# board.net
KiCad netlist of a schematic drawn in EAGLE
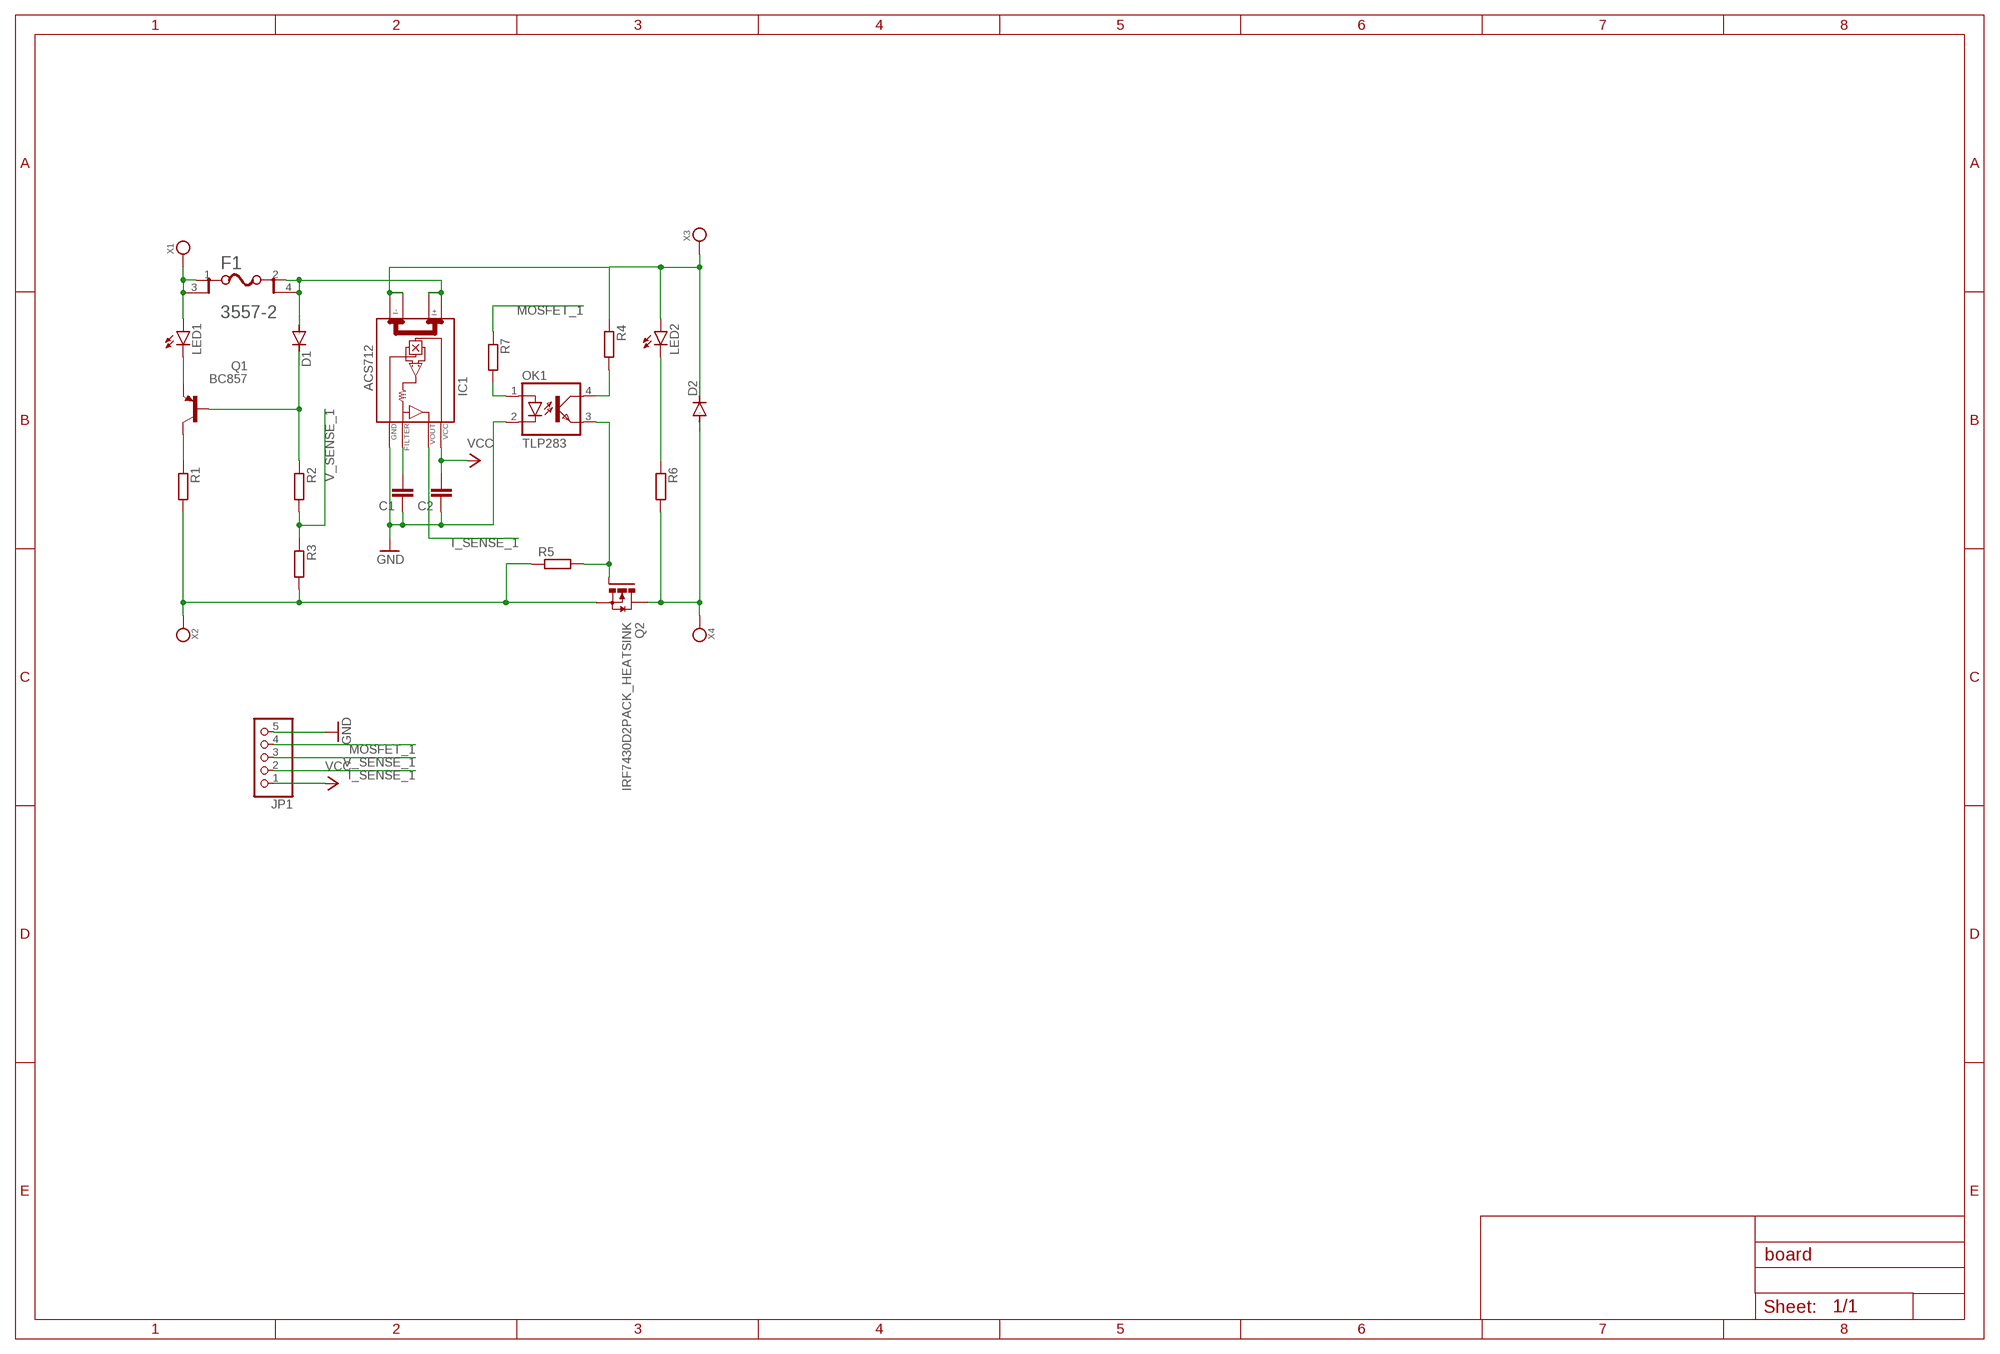
[diagram p0: schematic, sheet 1]

(export (version "E")
  (design (tool "Eeschema 10.0.6"))
  (components
    (comp (ref "C1")
      (value "C-EUC0805")
      (footprint "eagle-import:C0805")
      (libsource (lib "eagle-import") (part "C-EUC0805"))
    )
    (comp (ref "C2")
      (value "C-EUC0805")
      (footprint "eagle-import:C0805")
      (libsource (lib "eagle-import") (part "C-EUC0805"))
    )
    (comp (ref "D1")
      (value "DIODE-SOD123")
      (footprint "eagle-import:DIODE_SOD123")
      (libsource (lib "eagle-import") (part "DIODE-SOD123"))
    )
    (comp (ref "D2")
      (value "DIODE-DO214AC")
      (footprint "eagle-import:DO214AC")
      (libsource (lib "eagle-import") (part "diode_210_DIODE-DO214AC"))
    )
    (comp (ref "F1")
      (value "KEYSTONE_3557-2KEYSTONE_3557-2_0_0")
      (footprint "eagle-import:KEYSTONE_3557-2_0")
      (fields
        (field (name "DIGIKEY_PART_NUMBER") "36-3557-2-ND")
        (field (name "MF") "Keystone")
        (field (name "MOUSER_PART_NUMBER") "534-3557-2")
      )
      (libsource (lib "eagle-import") (part "KEYSTONE_3557-2KEYSTONE_3557-2_0_0"))
    )
    (comp (ref "IC1")
      (value "ACS712")
      (footprint "eagle-import:SO08")
      (libsource (lib "eagle-import") (part "ACS712"))
    )
    (comp (ref "JP1")
      (value "PINHD-1X5")
      (footprint "eagle-import:1X05")
      (libsource (lib "eagle-import") (part "PINHD-1X5"))
    )
    (comp (ref "LED1")
      (value "LEDSMT1206")
      (footprint "eagle-import:1206")
      (libsource (lib "eagle-import") (part "LEDSMT1206"))
    )
    (comp (ref "LED2")
      (value "LEDSMT1206")
      (footprint "eagle-import:1206")
      (libsource (lib "eagle-import") (part "LEDSMT1206"))
    )
    (comp (ref "OK1")
      (value "TLP283")
      (footprint "eagle-import:MINI-FLAT-4")
      (libsource (lib "eagle-import") (part "TLP283"))
    )
    (comp (ref "Q1")
      (value "BC857")
      (footprint "eagle-import:SOT23-BEC")
      (libsource (lib "eagle-import") (part "BC857SMDA"))
    )
    (comp (ref "Q2")
      (value "IRF7430D2PACK_HEATSINK")
      (footprint "eagle-import:D2PACK_HEATSINK")
      (libsource (lib "eagle-import") (part "IRF7430D2PACK_HEATSINK"))
    )
    (comp (ref "R1")
      (value "R-EU_R0805")
      (footprint "eagle-import:R0805")
      (libsource (lib "eagle-import") (part "R-EU_R0805"))
    )
    (comp (ref "R2")
      (value "R-EU_R0805")
      (footprint "eagle-import:R0805")
      (libsource (lib "eagle-import") (part "R-EU_R0805"))
    )
    (comp (ref "R3")
      (value "R-EU_R0805")
      (footprint "eagle-import:R0805")
      (libsource (lib "eagle-import") (part "R-EU_R0805"))
    )
    (comp (ref "R4")
      (value "R-EU_R0805")
      (footprint "eagle-import:R0805")
      (libsource (lib "eagle-import") (part "R-EU_R0805"))
    )
    (comp (ref "R5")
      (value "R-EU_R0805")
      (footprint "eagle-import:R0805")
      (libsource (lib "eagle-import") (part "R-EU_R0805"))
    )
    (comp (ref "R6")
      (value "R-EU_R0805")
      (footprint "eagle-import:R0805")
      (libsource (lib "eagle-import") (part "R-EU_R0805"))
    )
    (comp (ref "R7")
      (value "R-EU_R0805")
      (footprint "eagle-import:R0805")
      (libsource (lib "eagle-import") (part "R-EU_R0805"))
    )
    (comp (ref "X1")
      (value "7800")
      (footprint "eagle-import:7800")
      (libsource (lib "eagle-import") (part "7800"))
    )
    (comp (ref "X2")
      (value "7800")
      (footprint "eagle-import:7800")
      (libsource (lib "eagle-import") (part "7800"))
    )
    (comp (ref "X3")
      (value "7800")
      (footprint "eagle-import:7800")
      (libsource (lib "eagle-import") (part "7800"))
    )
    (comp (ref "X4")
      (value "7800")
      (footprint "eagle-import:7800")
      (libsource (lib "eagle-import") (part "7800"))
    )
  )
  (nets
    (net (code "1") (name "/I_SENSE_1") (class "Default")
      (node (ref "IC1") (pin "7") (pinfunction "VOUT_7") (pintype "output"))
      (node (ref "JP1") (pin "2") (pinfunction "2_2") (pintype "passive"))
    )
    (net (code "2") (name "/MOSFET_1") (class "Default")
      (node (ref "JP1") (pin "4") (pinfunction "4_4") (pintype "passive"))
      (node (ref "R7") (pin "1") (pinfunction "1_1") (pintype "passive"))
    )
    (net (code "3") (name "/V_SENSE_1") (class "Default")
      (node (ref "JP1") (pin "3") (pinfunction "3_3") (pintype "passive"))
      (node (ref "R2") (pin "2") (pinfunction "2_2") (pintype "passive"))
      (node (ref "R3") (pin "1") (pinfunction "1_1") (pintype "passive"))
    )
    (net (code "4") (name "GND") (class "Default")
      (node (ref "C1") (pin "1") (pinfunction "1_1") (pintype "passive"))
      (node (ref "C2") (pin "1") (pinfunction "1_1") (pintype "passive"))
      (node (ref "IC1") (pin "5") (pinfunction "GND_5") (pintype "power_in"))
      (node (ref "JP1") (pin "5") (pinfunction "5_5") (pintype "passive"))
      (node (ref "OK1") (pin "2") (pinfunction "C_2") (pintype "passive"))
    )
    (net (code "5") (name "Net-(D1-PadC)") (class "Default")
      (node (ref "D1") (pin "C") (pinfunction "C_C") (pintype "passive"))
      (node (ref "Q1") (pin "B") (pinfunction "B_B") (pintype "passive"))
      (node (ref "R2") (pin "1") (pinfunction "1_1") (pintype "passive"))
    )
    (net (code "6") (name "Net-(D2-PadA)") (class "Default")
      (node (ref "D2") (pin "A") (pinfunction "A_A") (pintype "passive"))
      (node (ref "Q2") (pin "2") (pinfunction "D_2") (pintype "passive"))
      (node (ref "Q2") (pin "4") (pinfunction "D_4") (pintype "passive"))
      (node (ref "Q2") (pin "5") (pinfunction "D_5") (pintype "passive"))
      (node (ref "R6") (pin "2") (pinfunction "2_2") (pintype "passive"))
      (node (ref "X4") (pin "1") (pinfunction "PIN_1") (pintype "bidirectional"))
      (node (ref "X4") (pin "2") (pinfunction "PIN_2") (pintype "bidirectional"))
      (node (ref "X4") (pin "3") (pinfunction "PIN_3") (pintype "bidirectional"))
      (node (ref "X4") (pin "4") (pinfunction "PIN_4") (pintype "bidirectional"))
      (node (ref "X4") (pin "5") (pinfunction "PIN_5") (pintype "bidirectional"))
      (node (ref "X4") (pin "6") (pinfunction "PIN_6") (pintype "bidirectional"))
    )
    (net (code "7") (name "Net-(F1-Pad1)") (class "Default")
      (node (ref "F1") (pin "1") (pinfunction "1_1") (pintype "bidirectional"))
      (node (ref "F1") (pin "3") (pinfunction "3_3") (pintype "bidirectional"))
      (node (ref "LED1") (pin "A") (pinfunction "A_A") (pintype "passive"))
      (node (ref "X1") (pin "1") (pinfunction "PIN_1") (pintype "bidirectional"))
      (node (ref "X1") (pin "2") (pinfunction "PIN_2") (pintype "bidirectional"))
      (node (ref "X1") (pin "3") (pinfunction "PIN_3") (pintype "bidirectional"))
      (node (ref "X1") (pin "4") (pinfunction "PIN_4") (pintype "bidirectional"))
      (node (ref "X1") (pin "5") (pinfunction "PIN_5") (pintype "bidirectional"))
      (node (ref "X1") (pin "6") (pinfunction "PIN_6") (pintype "bidirectional"))
    )
    (net (code "8") (name "Net-(IC1-FILTER)") (class "Default")
      (node (ref "C1") (pin "2") (pinfunction "2_2") (pintype "passive"))
      (node (ref "IC1") (pin "6") (pinfunction "FILTER_6") (pintype "bidirectional"))
    )
    (net (code "9") (name "Net-(IC1-I+_0)") (class "Default")
      (node (ref "D1") (pin "A") (pinfunction "A_A") (pintype "passive"))
      (node (ref "F1") (pin "2") (pinfunction "2_2") (pintype "bidirectional"))
      (node (ref "F1") (pin "4") (pinfunction "4_4") (pintype "bidirectional"))
      (node (ref "IC1") (pin "1") (pinfunction "I+_0_1") (pintype "bidirectional"))
      (node (ref "IC1") (pin "2") (pinfunction "I+_1_2") (pintype "bidirectional"))
    )
    (net (code "10") (name "Net-(IC1-I-_0)") (class "Default")
      (node (ref "D2") (pin "C") (pinfunction "C_C") (pintype "passive"))
      (node (ref "IC1") (pin "3") (pinfunction "I-_0_3") (pintype "bidirectional"))
      (node (ref "IC1") (pin "4") (pinfunction "I-_1_4") (pintype "bidirectional"))
      (node (ref "LED2") (pin "A") (pinfunction "A_A") (pintype "passive"))
      (node (ref "R4") (pin "1") (pinfunction "1_1") (pintype "passive"))
      (node (ref "X3") (pin "1") (pinfunction "PIN_1") (pintype "bidirectional"))
      (node (ref "X3") (pin "2") (pinfunction "PIN_2") (pintype "bidirectional"))
      (node (ref "X3") (pin "3") (pinfunction "PIN_3") (pintype "bidirectional"))
      (node (ref "X3") (pin "4") (pinfunction "PIN_4") (pintype "bidirectional"))
      (node (ref "X3") (pin "5") (pinfunction "PIN_5") (pintype "bidirectional"))
      (node (ref "X3") (pin "6") (pinfunction "PIN_6") (pintype "bidirectional"))
    )
    (net (code "11") (name "Net-(LED1-PadC)") (class "Default")
      (node (ref "LED1") (pin "C") (pinfunction "C_C") (pintype "passive"))
      (node (ref "Q1") (pin "E") (pinfunction "E_E") (pintype "passive"))
    )
    (net (code "12") (name "Net-(LED2-PadC)") (class "Default")
      (node (ref "LED2") (pin "C") (pinfunction "C_C") (pintype "passive"))
      (node (ref "R6") (pin "1") (pinfunction "1_1") (pintype "passive"))
    )
    (net (code "13") (name "Net-(OK1-A)") (class "Default")
      (node (ref "OK1") (pin "1") (pinfunction "A_1") (pintype "passive"))
      (node (ref "R7") (pin "2") (pinfunction "2_2") (pintype "passive"))
    )
    (net (code "14") (name "Net-(OK1-COL)") (class "Default")
      (node (ref "OK1") (pin "4") (pinfunction "COL_4") (pintype "passive"))
      (node (ref "R4") (pin "2") (pinfunction "2_2") (pintype "passive"))
    )
    (net (code "15") (name "Net-(OK1-EMIT)") (class "Default")
      (node (ref "OK1") (pin "3") (pinfunction "EMIT_3") (pintype "passive"))
      (node (ref "Q2") (pin "1") (pinfunction "G_1") (pintype "passive"))
      (node (ref "R5") (pin "2") (pinfunction "2_2") (pintype "passive"))
    )
    (net (code "16") (name "Net-(Q1-PadC)") (class "Default")
      (node (ref "Q1") (pin "C") (pinfunction "C_C") (pintype "passive"))
      (node (ref "R1") (pin "1") (pinfunction "1_1") (pintype "passive"))
    )
    (net (code "17") (name "Net-(Q2-S)") (class "Default")
      (node (ref "Q2") (pin "3") (pinfunction "S_3") (pintype "passive"))
      (node (ref "R1") (pin "2") (pinfunction "2_2") (pintype "passive"))
      (node (ref "R3") (pin "2") (pinfunction "2_2") (pintype "passive"))
      (node (ref "R5") (pin "1") (pinfunction "1_1") (pintype "passive"))
      (node (ref "X2") (pin "1") (pinfunction "PIN_1") (pintype "bidirectional"))
      (node (ref "X2") (pin "2") (pinfunction "PIN_2") (pintype "bidirectional"))
      (node (ref "X2") (pin "3") (pinfunction "PIN_3") (pintype "bidirectional"))
      (node (ref "X2") (pin "4") (pinfunction "PIN_4") (pintype "bidirectional"))
      (node (ref "X2") (pin "5") (pinfunction "PIN_5") (pintype "bidirectional"))
      (node (ref "X2") (pin "6") (pinfunction "PIN_6") (pintype "bidirectional"))
    )
    (net (code "18") (name "VCC") (class "Default")
      (node (ref "C2") (pin "2") (pinfunction "2_2") (pintype "passive"))
      (node (ref "IC1") (pin "8") (pinfunction "VCC_8") (pintype "power_in"))
      (node (ref "JP1") (pin "1") (pinfunction "1_1") (pintype "passive"))
    )
  )
)
